# fauxmo-smd.net
KiCad netlist of a schematic drawn in EAGLE
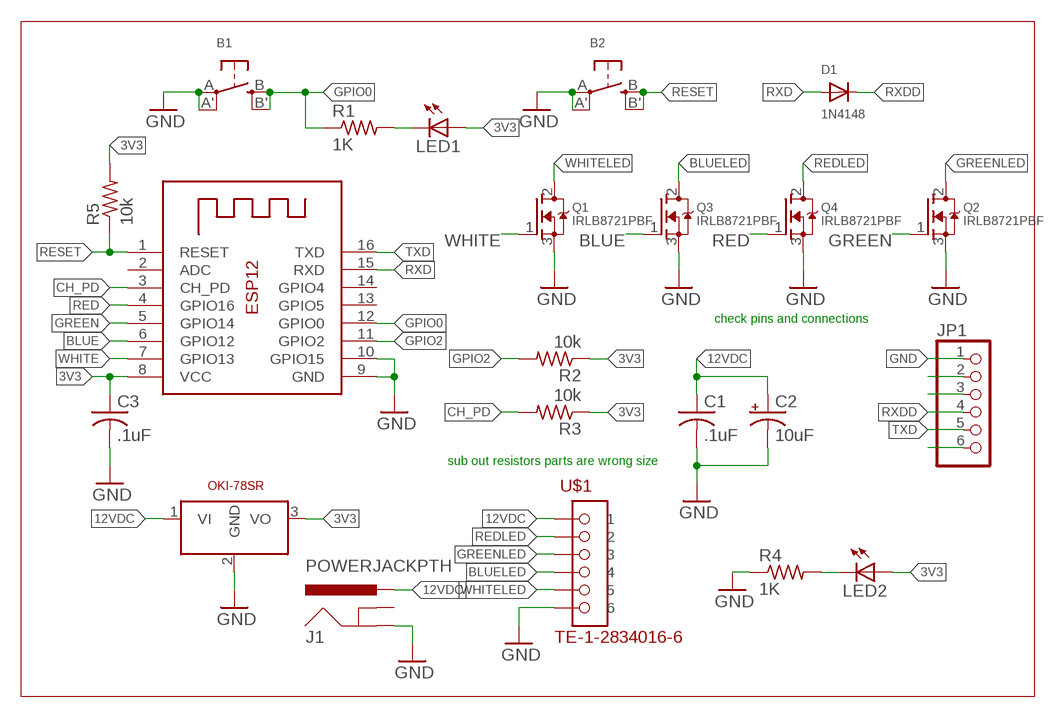
[diagram p0: schematic, sheet 1]

(export (version "E")
  (design (tool "Eeschema 10.0.6"))
  (components
    (comp (ref "B1")
      (value "SWITCH_TACT_SMT")
      (footprint "eagle-import:EVQ-Q2")
      (libsource (lib "eagle-import") (part "SWITCH_TACT_SMT"))
    )
    (comp (ref "B2")
      (value "SWITCH_TACT_SMT")
      (footprint "eagle-import:EVQ-Q2")
      (libsource (lib "eagle-import") (part "SWITCH_TACT_SMT"))
    )
    (comp (ref "C1")
      (value ".1uF")
      (footprint "eagle-import:C0805")
      (libsource (lib "eagle-import") (part "C-USC0805"))
    )
    (comp (ref "C2")
      (value "10uF")
      (footprint "eagle-import:E2,5-5")
      (libsource (lib "eagle-import") (part "CPOL-USE2.5-5"))
    )
    (comp (ref "C3")
      (value ".1uF")
      (footprint "eagle-import:C0805")
      (libsource (lib "eagle-import") (part "C-USC0805"))
    )
    (comp (ref "D1")
      (value "1N4148")
      (footprint "eagle-import:SOD-123")
      (libsource (lib "eagle-import") (part "DIODESOD-123"))
    )
    (comp (ref "J1")
      (value "POWERJACKPTH")
      (footprint "eagle-import:BARREL-2.1")
      (libsource (lib "eagle-import") (part "POWERJACKPTH"))
    )
    (comp (ref "JP1")
      (value "PINHD-1X6")
      (footprint "eagle-import:1X06")
      (libsource (lib "eagle-import") (part "PINHD-1X6"))
    )
    (comp (ref "LED1")
      (value "LEDCHIP-LED0805")
      (footprint "eagle-import:CHIP-LED0805")
      (libsource (lib "eagle-import") (part "LEDCHIP-LED0805"))
    )
    (comp (ref "LED2")
      (value "LEDCHIP-LED0805")
      (footprint "eagle-import:CHIP-LED0805")
      (libsource (lib "eagle-import") (part "LEDCHIP-LED0805"))
    )
    (comp (ref "OKI")
      (value "DCDC_OKI-78SROKI-78SRV")
      (footprint "eagle-import:OKI-78SRH")
      (libsource (lib "eagle-import") (part "DCDC_OKI-78SROKI-78SRV"))
    )
    (comp (ref "Q1")
      (value "IRLB8721PBF")
      (footprint "eagle-import:TO220V")
      (libsource (lib "eagle-import") (part "MOSFET-NGDS_TO220V"))
    )
    (comp (ref "Q2")
      (value "IRLB8721PBF")
      (footprint "eagle-import:TO220V")
      (libsource (lib "eagle-import") (part "MOSFET-NGDS_TO220V"))
    )
    (comp (ref "Q3")
      (value "IRLB8721PBF")
      (footprint "eagle-import:TO220V")
      (libsource (lib "eagle-import") (part "MOSFET-NGDS_TO220V"))
    )
    (comp (ref "Q4")
      (value "IRLB8721PBF")
      (footprint "eagle-import:TO220V")
      (libsource (lib "eagle-import") (part "MOSFET-NGDS_TO220V"))
    )
    (comp (ref "R1")
      (value "1K")
      (footprint "eagle-import:R0805")
      (libsource (lib "eagle-import") (part "R-US_R0805"))
    )
    (comp (ref "R2")
      (value "10k")
      (footprint "eagle-import:R0805")
      (libsource (lib "eagle-import") (part "R-US_R0805"))
    )
    (comp (ref "R3")
      (value "10k")
      (footprint "eagle-import:R0805")
      (libsource (lib "eagle-import") (part "R-US_R0805"))
    )
    (comp (ref "R4")
      (value "1K")
      (footprint "eagle-import:R0805")
      (libsource (lib "eagle-import") (part "R-US_R0805"))
    )
    (comp (ref "R5")
      (value "10k")
      (footprint "eagle-import:R0805")
      (libsource (lib "eagle-import") (part "R-US_R0805"))
    )
    (comp (ref "U$1")
      (value "TE-1-2834016-6")
      (footprint "eagle-import:TE-1-2834016-6")
      (libsource (lib "eagle-import") (part "TE-1-2834016-6"))
    )
    (comp (ref "X1")
      (value "ESP-12")
      (footprint "eagle-import:ESP-12")
      (libsource (lib "eagle-import") (part "ESP-12"))
    )
  )
  (nets
    (net (code "1") (name "3V3") (class "Default")
      (node (ref "C3") (pin "1") (pinfunction "1_1") (pintype "passive"))
      (node (ref "LED1") (pin "A") (pinfunction "A_A") (pintype "passive"))
      (node (ref "LED2") (pin "A") (pinfunction "A_A") (pintype "passive"))
      (node (ref "OKI") (pin "3") (pinfunction "VO_3") (pintype "bidirectional"))
      (node (ref "R2") (pin "1") (pinfunction "1_1") (pintype "passive"))
      (node (ref "R3") (pin "1") (pinfunction "1_1") (pintype "passive"))
      (node (ref "R5") (pin "2") (pinfunction "2_2") (pintype "passive"))
      (node (ref "X1") (pin "8") (pinfunction "VCC_8") (pintype "power_in"))
    )
    (net (code "2") (name "12VDC") (class "Default")
      (node (ref "C1") (pin "1") (pinfunction "1_1") (pintype "passive"))
      (node (ref "C2") (pin "+") (pinfunction "+_+") (pintype "passive"))
      (node (ref "J1") (pin "PWR") (pinfunction "PWR_PWR") (pintype "bidirectional"))
      (node (ref "OKI") (pin "1") (pinfunction "VI_1") (pintype "bidirectional"))
      (node (ref "U$1") (pin "P$6") (pinfunction "1_P$6") (pintype "bidirectional"))
    )
    (net (code "3") (name "BLUE") (class "Default")
      (node (ref "Q3") (pin "1") (pinfunction "G_1") (pintype "bidirectional"))
      (node (ref "X1") (pin "6") (pinfunction "GPIO12_6") (pintype "bidirectional"))
    )
    (net (code "4") (name "BLUELED") (class "Default")
      (node (ref "Q3") (pin "2") (pinfunction "D_2") (pintype "bidirectional"))
      (node (ref "U$1") (pin "P$3") (pinfunction "4_P$3") (pintype "bidirectional"))
    )
    (net (code "5") (name "CH_PD") (class "Default")
      (node (ref "R3") (pin "2") (pinfunction "2_2") (pintype "passive"))
      (node (ref "X1") (pin "3") (pinfunction "CH_PD_3") (pintype "input"))
    )
    (net (code "6") (name "GND") (class "Default")
      (node (ref "B1") (pin "A") (pinfunction "P_A") (pintype "passive"))
      (node (ref "B1") (pin "A'") (pinfunction "P1_A'") (pintype "passive"))
      (node (ref "B2") (pin "A") (pinfunction "P_A") (pintype "passive"))
      (node (ref "B2") (pin "A'") (pinfunction "P1_A'") (pintype "passive"))
      (node (ref "C1") (pin "2") (pinfunction "2_2") (pintype "passive"))
      (node (ref "C2") (pin "-") (pinfunction "-_-") (pintype "passive"))
      (node (ref "C3") (pin "2") (pinfunction "2_2") (pintype "passive"))
      (node (ref "J1") (pin "GND") (pinfunction "GND_GND") (pintype "bidirectional"))
      (node (ref "JP1") (pin "1") (pinfunction "1_1") (pintype "passive"))
      (node (ref "OKI") (pin "2") (pinfunction "GND_2") (pintype "bidirectional"))
      (node (ref "Q1") (pin "3") (pinfunction "S_3") (pintype "bidirectional"))
      (node (ref "Q2") (pin "3") (pinfunction "S_3") (pintype "bidirectional"))
      (node (ref "Q3") (pin "3") (pinfunction "S_3") (pintype "bidirectional"))
      (node (ref "Q4") (pin "3") (pinfunction "S_3") (pintype "bidirectional"))
      (node (ref "R4") (pin "1") (pinfunction "1_1") (pintype "passive"))
      (node (ref "U$1") (pin "P$1") (pinfunction "6_P$1") (pintype "bidirectional"))
      (node (ref "X1") (pin "10") (pinfunction "GPIO15_10") (pintype "bidirectional"))
      (node (ref "X1") (pin "9") (pinfunction "GND_9") (pintype "power_in"))
    )
    (net (code "7") (name "GPIO0") (class "Default")
      (node (ref "B1") (pin "B") (pinfunction "S_B") (pintype "passive"))
      (node (ref "B1") (pin "B'") (pinfunction "S1_B'") (pintype "passive"))
      (node (ref "R1") (pin "1") (pinfunction "1_1") (pintype "passive"))
      (node (ref "X1") (pin "12") (pinfunction "GPIO0_12") (pintype "bidirectional"))
    )
    (net (code "8") (name "GPIO2") (class "Default")
      (node (ref "R2") (pin "2") (pinfunction "2_2") (pintype "passive"))
      (node (ref "X1") (pin "11") (pinfunction "GPIO2_11") (pintype "bidirectional"))
    )
    (net (code "9") (name "GREEN") (class "Default")
      (node (ref "Q2") (pin "1") (pinfunction "G_1") (pintype "bidirectional"))
      (node (ref "X1") (pin "5") (pinfunction "GPIO14_5") (pintype "bidirectional"))
    )
    (net (code "10") (name "GREENLED") (class "Default")
      (node (ref "Q2") (pin "2") (pinfunction "D_2") (pintype "bidirectional"))
      (node (ref "U$1") (pin "P$4") (pinfunction "3_P$4") (pintype "bidirectional"))
    )
    (net (code "11") (name "Net-(LED1-PadC)") (class "Default")
      (node (ref "LED1") (pin "C") (pinfunction "C_C") (pintype "passive"))
      (node (ref "R1") (pin "2") (pinfunction "2_2") (pintype "passive"))
    )
    (net (code "12") (name "Net-(LED2-PadC)") (class "Default")
      (node (ref "LED2") (pin "C") (pinfunction "C_C") (pintype "passive"))
      (node (ref "R4") (pin "2") (pinfunction "2_2") (pintype "passive"))
    )
    (net (code "13") (name "RED") (class "Default")
      (node (ref "Q4") (pin "1") (pinfunction "G_1") (pintype "bidirectional"))
      (node (ref "X1") (pin "4") (pinfunction "GPIO16_4") (pintype "bidirectional"))
    )
    (net (code "14") (name "REDLED") (class "Default")
      (node (ref "Q4") (pin "2") (pinfunction "D_2") (pintype "bidirectional"))
      (node (ref "U$1") (pin "P$5") (pinfunction "2_P$5") (pintype "bidirectional"))
    )
    (net (code "15") (name "RESET") (class "Default")
      (node (ref "B2") (pin "B") (pinfunction "S_B") (pintype "passive"))
      (node (ref "B2") (pin "B'") (pinfunction "S1_B'") (pintype "passive"))
      (node (ref "R5") (pin "1") (pinfunction "1_1") (pintype "passive"))
      (node (ref "X1") (pin "1") (pinfunction "RESET_1") (pintype "input"))
    )
    (net (code "16") (name "RXD") (class "Default")
      (node (ref "D1") (pin "A") (pinfunction "A_A") (pintype "passive"))
      (node (ref "X1") (pin "15") (pinfunction "RXD_15") (pintype "input"))
    )
    (net (code "17") (name "RXDD") (class "Default")
      (node (ref "D1") (pin "C") (pinfunction "C_C") (pintype "passive"))
      (node (ref "JP1") (pin "4") (pinfunction "4_4") (pintype "passive"))
    )
    (net (code "18") (name "TXD") (class "Default")
      (node (ref "JP1") (pin "5") (pinfunction "5_5") (pintype "passive"))
      (node (ref "X1") (pin "16") (pinfunction "TXD_16") (pintype "output"))
    )
    (net (code "19") (name "WHITE") (class "Default")
      (node (ref "Q1") (pin "1") (pinfunction "G_1") (pintype "bidirectional"))
      (node (ref "X1") (pin "7") (pinfunction "GPIO13_7") (pintype "bidirectional"))
    )
    (net (code "20") (name "WHITELED") (class "Default")
      (node (ref "Q1") (pin "2") (pinfunction "D_2") (pintype "bidirectional"))
      (node (ref "U$1") (pin "P$2") (pinfunction "5_P$2") (pintype "bidirectional"))
    )
    (net (code "21") (name "unconnected-(J1-PadGNDBREAK)") (class "Default")
      (node (ref "J1") (pin "GNDBREAK") (pinfunction "GNDBREAK_GNDBREAK") (pintype "bidirectional"))
    )
    (net (code "22") (name "unconnected-(JP1-Pad2)") (class "Default")
      (node (ref "JP1") (pin "2") (pinfunction "2_2") (pintype "passive"))
    )
    (net (code "23") (name "unconnected-(JP1-Pad3)") (class "Default")
      (node (ref "JP1") (pin "3") (pinfunction "3_3") (pintype "passive"))
    )
    (net (code "24") (name "unconnected-(JP1-Pad6)") (class "Default")
      (node (ref "JP1") (pin "6") (pinfunction "6_6") (pintype "passive"))
    )
    (net (code "25") (name "unconnected-(X1-ADC-Pad2)") (class "Default")
      (node (ref "X1") (pin "2") (pinfunction "ADC_2") (pintype "passive"))
    )
    (net (code "26") (name "unconnected-(X1-GPIO4-Pad14)") (class "Default")
      (node (ref "X1") (pin "14") (pinfunction "GPIO4_14") (pintype "bidirectional"))
    )
    (net (code "27") (name "unconnected-(X1-GPIO5-Pad13)") (class "Default")
      (node (ref "X1") (pin "13") (pinfunction "GPIO5_13") (pintype "bidirectional"))
    )
  )
)
